# Micro-OLED-Breakout.net
KiCad netlist of a schematic drawn in EAGLE
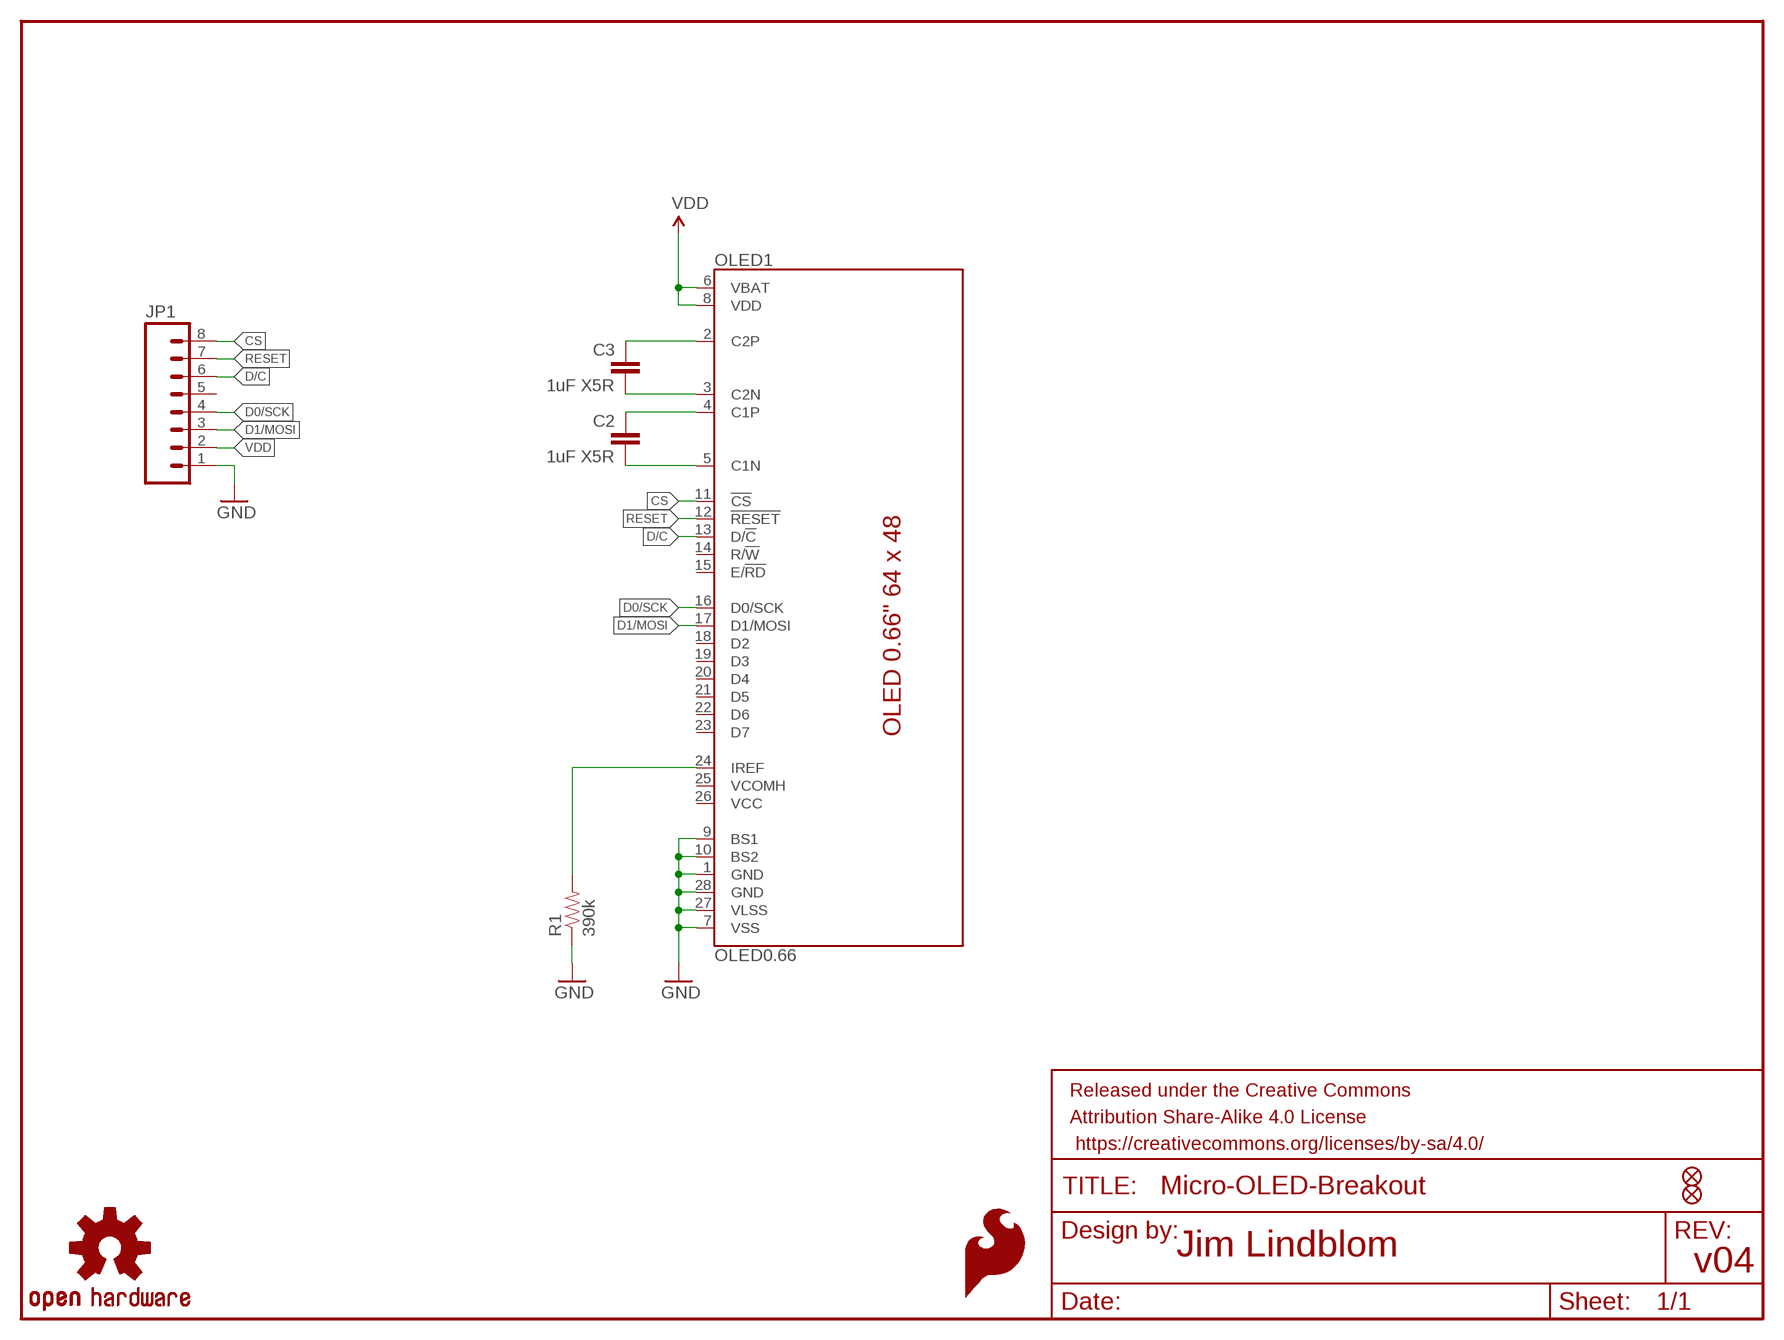
[diagram p0: schematic, sheet 1]

(export (version "E")
  (design (tool "Eeschema 10.0.6"))
  (components
    (comp (ref "C2")
      (value "1uF X5R")
      (footprint "eagle-import:0805")
      (libsource (lib "eagle-import") (part "CAP0805"))
    )
    (comp (ref "C3")
      (value "1uF X5R")
      (footprint "eagle-import:0805")
      (libsource (lib "eagle-import") (part "CAP0805"))
    )
    (comp (ref "FID1")
      (value "FIDUCIAL1X2")
      (footprint "eagle-import:FIDUCIAL-1X2")
      (libsource (lib "eagle-import") (part "FIDUCIAL1X2"))
    )
    (comp (ref "FID2")
      (value "FIDUCIAL1X2")
      (footprint "eagle-import:FIDUCIAL-1X2")
      (libsource (lib "eagle-import") (part "FIDUCIAL1X2"))
    )
    (comp (ref "FRAME1")
      (value "FRAME-LETTER")
      (footprint "eagle-import:CREATIVE_COMMONS")
      (libsource (lib "eagle-import") (part "FRAME-LETTER"))
    )
    (comp (ref "JP1")
      (value "M08")
      (footprint "eagle-import:1X08_PIN1_NO_SILK")
      (libsource (lib "eagle-import") (part "M08"))
    )
    (comp (ref "LOGO3")
      (value "OSHW-LOGOS")
      (footprint "eagle-import:OSHW-LOGO-S")
      (libsource (lib "eagle-import") (part "OSHW-LOGOS"))
    )
    (comp (ref "LOGO4")
      (value "SFE_LOGO_FLAME.1_INCH")
      (footprint "eagle-import:SFE_LOGO_FLAME_.1")
      (libsource (lib "eagle-import") (part "SFE_LOGO_FLAME.1_INCH"))
    )
    (comp (ref "OLED1")
      (value "OLED0.66")
      (footprint "eagle-import:OLED-0.66-64X48")
      (libsource (lib "eagle-import") (part "OLED0.66"))
    )
    (comp (ref "R1")
      (value "390k")
      (footprint "eagle-import:0603-RES")
      (libsource (lib "eagle-import") (part "RESISTOR0603-RES"))
    )
  )
  (nets
    (net (code "1") (name "CS") (class "Default")
      (node (ref "JP1") (pin "8") (pinfunction "8_8") (pintype "passive"))
      (node (ref "OLED1") (pin "11") (pinfunction "~{CS}_11") (pintype "bidirectional"))
    )
    (net (code "2") (name "D0{slash}SCK") (class "Default")
      (node (ref "JP1") (pin "4") (pinfunction "4_4") (pintype "passive"))
      (node (ref "OLED1") (pin "16") (pinfunction "D0/SCK_16") (pintype "bidirectional"))
    )
    (net (code "3") (name "D1{slash}MOSI") (class "Default")
      (node (ref "JP1") (pin "3") (pinfunction "3_3") (pintype "passive"))
      (node (ref "OLED1") (pin "17") (pinfunction "D1/MOSI_17") (pintype "bidirectional"))
    )
    (net (code "4") (name "D{slash}C") (class "Default")
      (node (ref "JP1") (pin "6") (pinfunction "6_6") (pintype "passive"))
      (node (ref "OLED1") (pin "13") (pinfunction "D/~{C}_13") (pintype "bidirectional"))
    )
    (net (code "5") (name "GND") (class "Default")
      (node (ref "JP1") (pin "1") (pinfunction "1_1") (pintype "passive"))
      (node (ref "OLED1") (pin "1") (pinfunction "GND_1") (pintype "bidirectional"))
      (node (ref "OLED1") (pin "10") (pinfunction "BS2_10") (pintype "bidirectional"))
      (node (ref "OLED1") (pin "27") (pinfunction "VLSS_27") (pintype "bidirectional"))
      (node (ref "OLED1") (pin "28") (pinfunction "GND_28") (pintype "bidirectional"))
      (node (ref "OLED1") (pin "7") (pinfunction "VSS_7") (pintype "bidirectional"))
      (node (ref "OLED1") (pin "9") (pinfunction "BS1_9") (pintype "bidirectional"))
      (node (ref "R1") (pin "1") (pinfunction "1_1") (pintype "passive"))
    )
    (net (code "6") (name "Net-(OLED1-C1N)") (class "Default")
      (node (ref "C2") (pin "2") (pinfunction "2_2") (pintype "passive"))
      (node (ref "OLED1") (pin "5") (pinfunction "C1N_5") (pintype "bidirectional"))
    )
    (net (code "7") (name "Net-(OLED1-C1P)") (class "Default")
      (node (ref "C2") (pin "1") (pinfunction "1_1") (pintype "passive"))
      (node (ref "OLED1") (pin "4") (pinfunction "C1P_4") (pintype "bidirectional"))
    )
    (net (code "8") (name "Net-(OLED1-C2N)") (class "Default")
      (node (ref "C3") (pin "2") (pinfunction "2_2") (pintype "passive"))
      (node (ref "OLED1") (pin "3") (pinfunction "C2N_3") (pintype "bidirectional"))
    )
    (net (code "9") (name "Net-(OLED1-C2P)") (class "Default")
      (node (ref "C3") (pin "1") (pinfunction "1_1") (pintype "passive"))
      (node (ref "OLED1") (pin "2") (pinfunction "C2P_2") (pintype "bidirectional"))
    )
    (net (code "10") (name "Net-(OLED1-IREF)") (class "Default")
      (node (ref "OLED1") (pin "24") (pinfunction "IREF_24") (pintype "bidirectional"))
      (node (ref "R1") (pin "2") (pinfunction "2_2") (pintype "passive"))
    )
    (net (code "11") (name "RESET") (class "Default")
      (node (ref "JP1") (pin "7") (pinfunction "7_7") (pintype "passive"))
      (node (ref "OLED1") (pin "12") (pinfunction "~{RESET}_12") (pintype "bidirectional"))
    )
    (net (code "12") (name "VDD") (class "Default")
      (node (ref "JP1") (pin "2") (pinfunction "2_2") (pintype "passive"))
      (node (ref "OLED1") (pin "6") (pinfunction "VBAT_6") (pintype "bidirectional"))
      (node (ref "OLED1") (pin "8") (pinfunction "VDD_8") (pintype "bidirectional"))
    )
    (net (code "13") (name "unconnected-(JP1-Pad5)") (class "Default")
      (node (ref "JP1") (pin "5") (pinfunction "5_5") (pintype "passive"))
    )
    (net (code "14") (name "unconnected-(OLED1-D2-Pad18)") (class "Default")
      (node (ref "OLED1") (pin "18") (pinfunction "D2_18") (pintype "bidirectional"))
    )
    (net (code "15") (name "unconnected-(OLED1-D3-Pad19)") (class "Default")
      (node (ref "OLED1") (pin "19") (pinfunction "D3_19") (pintype "bidirectional"))
    )
    (net (code "16") (name "unconnected-(OLED1-D4-Pad20)") (class "Default")
      (node (ref "OLED1") (pin "20") (pinfunction "D4_20") (pintype "bidirectional"))
    )
    (net (code "17") (name "unconnected-(OLED1-D5-Pad21)") (class "Default")
      (node (ref "OLED1") (pin "21") (pinfunction "D5_21") (pintype "bidirectional"))
    )
    (net (code "18") (name "unconnected-(OLED1-D6-Pad22)") (class "Default")
      (node (ref "OLED1") (pin "22") (pinfunction "D6_22") (pintype "bidirectional"))
    )
    (net (code "19") (name "unconnected-(OLED1-D7-Pad23)") (class "Default")
      (node (ref "OLED1") (pin "23") (pinfunction "D7_23") (pintype "bidirectional"))
    )
    (net (code "20") (name "unconnected-(OLED1-E{slash}~{RD}-Pad15)") (class "Default")
      (node (ref "OLED1") (pin "15") (pinfunction "E/~{RD}_15") (pintype "bidirectional"))
    )
    (net (code "21") (name "unconnected-(OLED1-R{slash}~{W}-Pad14)") (class "Default")
      (node (ref "OLED1") (pin "14") (pinfunction "R/~{W}_14") (pintype "bidirectional"))
    )
    (net (code "22") (name "unconnected-(OLED1-VCC-Pad26)") (class "Default")
      (node (ref "OLED1") (pin "26") (pinfunction "VCC_26") (pintype "bidirectional"))
    )
    (net (code "23") (name "unconnected-(OLED1-VCOMH-Pad25)") (class "Default")
      (node (ref "OLED1") (pin "25") (pinfunction "VCOMH_25") (pintype "bidirectional"))
    )
  )
)
